# KranPowerV2_1.net
KiCad netlist of a schematic drawn in EAGLE
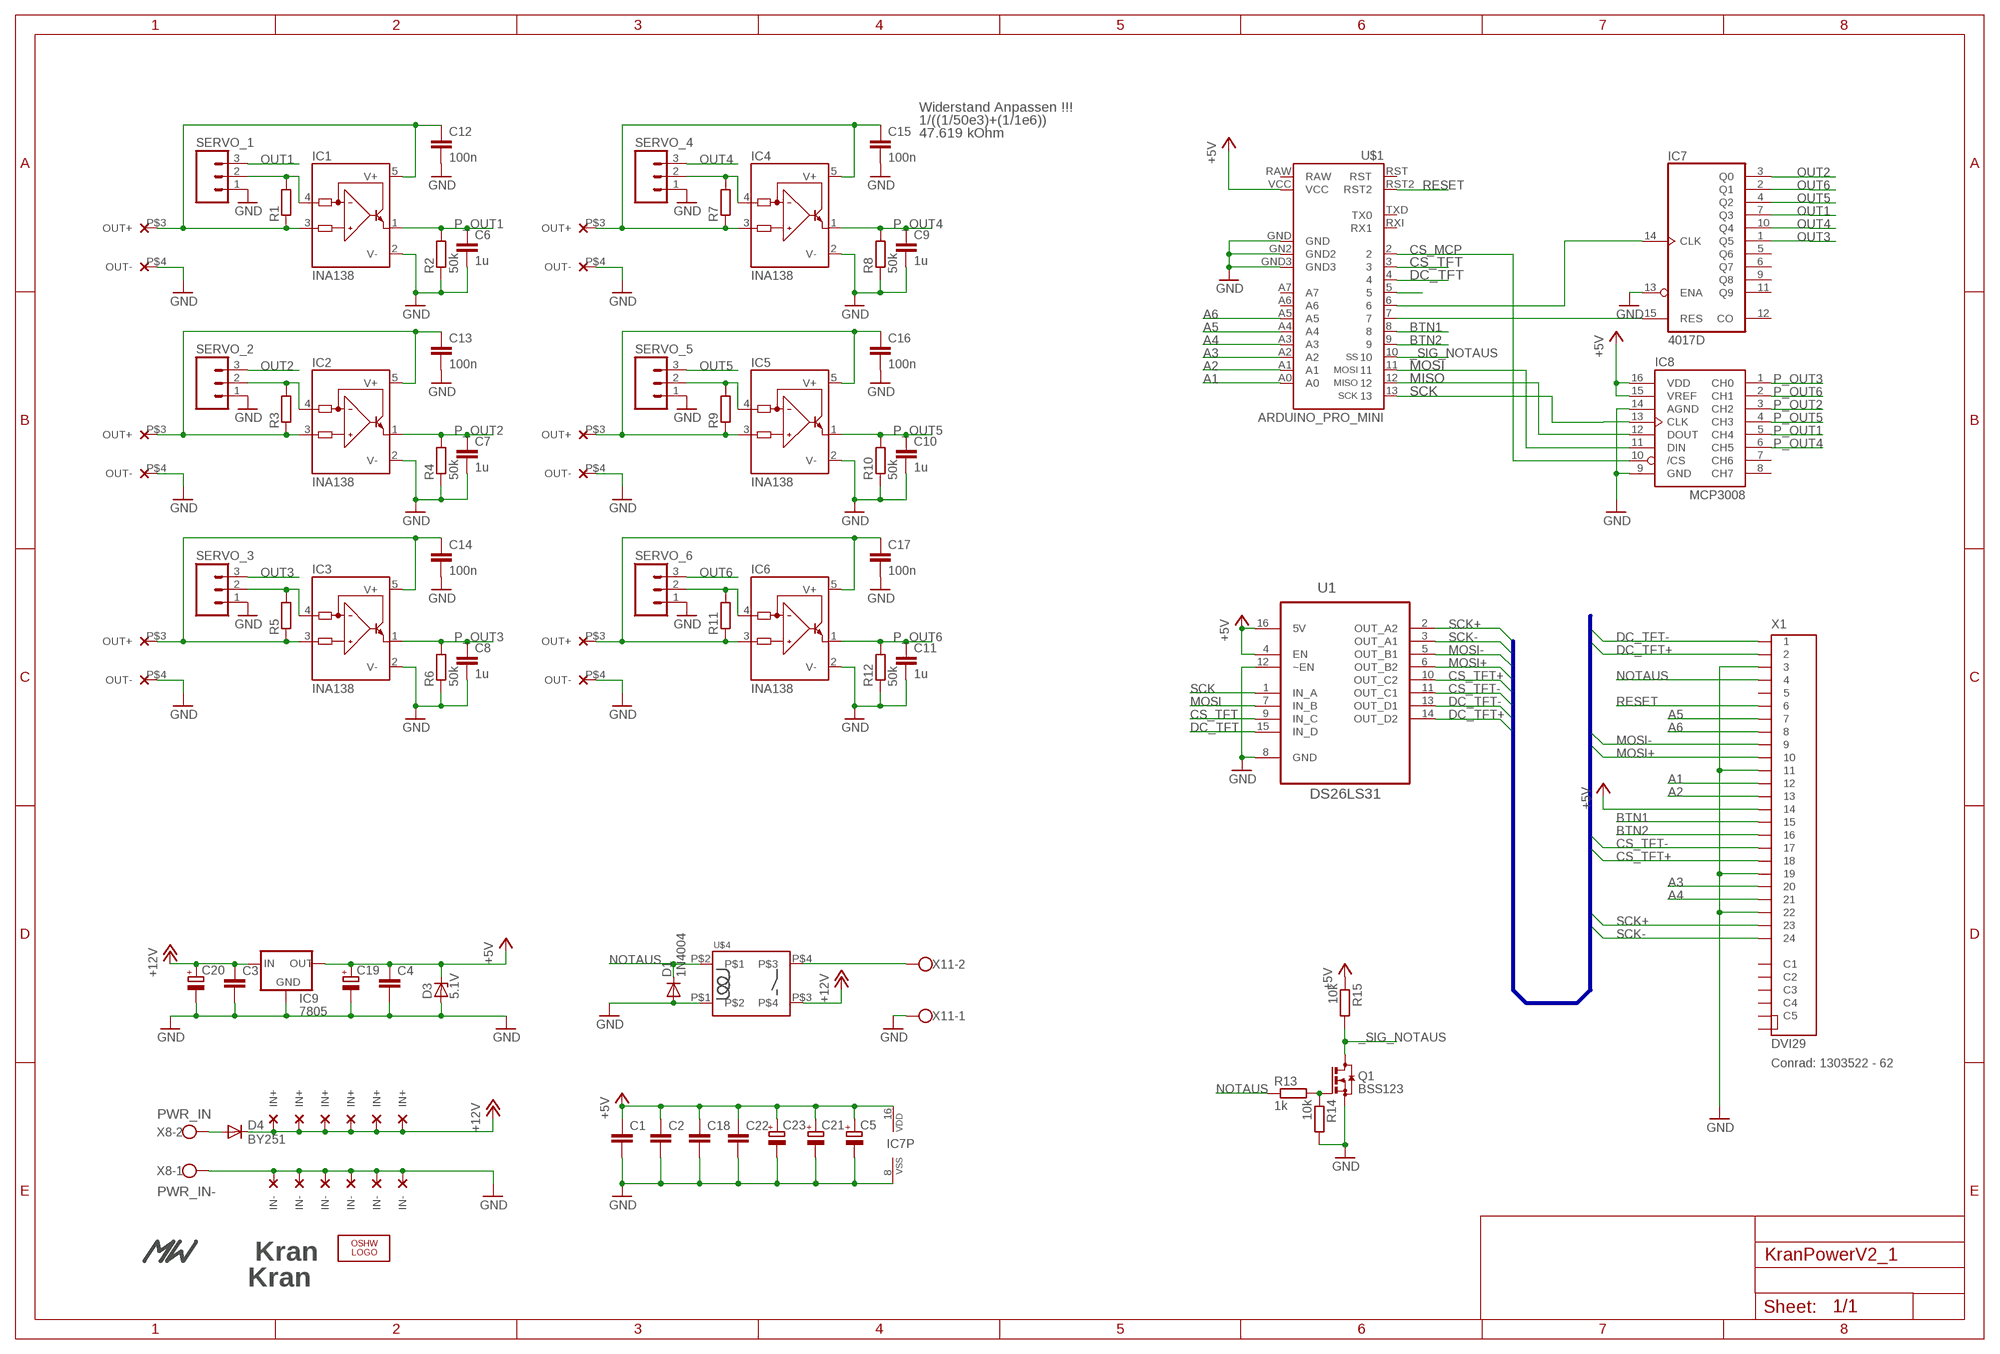
[diagram p0: schematic, sheet 1]

(export (version "E")
  (design (tool "Eeschema 10.0.6"))
  (components
    (comp (ref "C1")
      (value "C-EUC0603")
      (footprint "eagle-import:C0603")
      (libsource (lib "eagle-import") (part "C-EUC0603"))
    )
    (comp (ref "C2")
      (value "C-EUC0603")
      (footprint "eagle-import:C0603")
      (libsource (lib "eagle-import") (part "C-EUC0603"))
    )
    (comp (ref "C3")
      (value "C-EUC0603")
      (footprint "eagle-import:C0603")
      (libsource (lib "eagle-import") (part "C-EUC0603"))
    )
    (comp (ref "C4")
      (value "C-EUC0603")
      (footprint "eagle-import:C0603")
      (libsource (lib "eagle-import") (part "C-EUC0603"))
    )
    (comp (ref "C5")
      (value "CPOL-EUSMCB")
      (footprint "eagle-import:SMC_B")
      (libsource (lib "eagle-import") (part "CPOL-EUSMCB"))
    )
    (comp (ref "C6")
      (value "1u")
      (footprint "eagle-import:C0603")
      (libsource (lib "eagle-import") (part "C-EUC0603"))
    )
    (comp (ref "C7")
      (value "1u")
      (footprint "eagle-import:C0603")
      (libsource (lib "eagle-import") (part "C-EUC0603"))
    )
    (comp (ref "C8")
      (value "1u")
      (footprint "eagle-import:C0603")
      (libsource (lib "eagle-import") (part "C-EUC0603"))
    )
    (comp (ref "C9")
      (value "1u")
      (footprint "eagle-import:C0603")
      (libsource (lib "eagle-import") (part "C-EUC0603"))
    )
    (comp (ref "C10")
      (value "1u")
      (footprint "eagle-import:C0603")
      (libsource (lib "eagle-import") (part "C-EUC0603"))
    )
    (comp (ref "C11")
      (value "1u")
      (footprint "eagle-import:C0603")
      (libsource (lib "eagle-import") (part "C-EUC0603"))
    )
    (comp (ref "C12")
      (value "100n")
      (footprint "eagle-import:C0603")
      (libsource (lib "eagle-import") (part "C-EUC0603"))
    )
    (comp (ref "C13")
      (value "100n")
      (footprint "eagle-import:C0603")
      (libsource (lib "eagle-import") (part "C-EUC0603"))
    )
    (comp (ref "C14")
      (value "100n")
      (footprint "eagle-import:C0603")
      (libsource (lib "eagle-import") (part "C-EUC0603"))
    )
    (comp (ref "C15")
      (value "100n")
      (footprint "eagle-import:C0603")
      (libsource (lib "eagle-import") (part "C-EUC0603"))
    )
    (comp (ref "C16")
      (value "100n")
      (footprint "eagle-import:C0603")
      (libsource (lib "eagle-import") (part "C-EUC0603"))
    )
    (comp (ref "C17")
      (value "100n")
      (footprint "eagle-import:C0603")
      (libsource (lib "eagle-import") (part "C-EUC0603"))
    )
    (comp (ref "C18")
      (value "C-EUC0603")
      (footprint "eagle-import:C0603")
      (libsource (lib "eagle-import") (part "C-EUC0603"))
    )
    (comp (ref "C19")
      (value "CPOL-EUSMCB")
      (footprint "eagle-import:SMC_B")
      (libsource (lib "eagle-import") (part "CPOL-EUSMCB"))
    )
    (comp (ref "C20")
      (value "CPOL-EUSMCB")
      (footprint "eagle-import:SMC_B")
      (libsource (lib "eagle-import") (part "CPOL-EUSMCB"))
    )
    (comp (ref "C21")
      (value "CPOL-EUSMCB")
      (footprint "eagle-import:SMC_B")
      (libsource (lib "eagle-import") (part "CPOL-EUSMCB"))
    )
    (comp (ref "C22")
      (value "C-EUC0603")
      (footprint "eagle-import:C0603")
      (libsource (lib "eagle-import") (part "C-EUC0603"))
    )
    (comp (ref "C23")
      (value "CPOL-EUSMCB")
      (footprint "eagle-import:SMC_B")
      (libsource (lib "eagle-import") (part "CPOL-EUSMCB"))
    )
    (comp (ref "D1")
      (value "1N4004")
      (footprint "eagle-import:DO41-10")
      (libsource (lib "eagle-import") (part "1N4004"))
    )
    (comp (ref "D3")
      (value "5.1V")
      (footprint "eagle-import:DO34Z7")
      (libsource (lib "eagle-import") (part "ZENER-DIODEDO34-7"))
    )
    (comp (ref "D4")
      (value "BY251")
      (footprint "eagle-import:DO201-15")
      (libsource (lib "eagle-import") (part "BY251"))
    )
    (comp (ref "IC1")
      (value "INA138")
      (footprint "eagle-import:SOT23-5")
      (fields (field (name "MF") "TEXAS INSTRUMENTS") (field (name "MPN") "INA138NA/250"))
      (libsource (lib "eagle-import") (part "INA138"))
    )
    (comp (ref "IC2")
      (value "INA138")
      (footprint "eagle-import:SOT23-5")
      (fields (field (name "MF") "TEXAS INSTRUMENTS") (field (name "MPN") "INA138NA/250"))
      (libsource (lib "eagle-import") (part "INA138"))
    )
    (comp (ref "IC3")
      (value "INA138")
      (footprint "eagle-import:SOT23-5")
      (fields (field (name "MF") "TEXAS INSTRUMENTS") (field (name "MPN") "INA138NA/250"))
      (libsource (lib "eagle-import") (part "INA138"))
    )
    (comp (ref "IC4")
      (value "INA138")
      (footprint "eagle-import:SOT23-5")
      (fields (field (name "MF") "TEXAS INSTRUMENTS") (field (name "MPN") "INA138NA/250"))
      (libsource (lib "eagle-import") (part "INA138"))
    )
    (comp (ref "IC5")
      (value "INA138")
      (footprint "eagle-import:SOT23-5")
      (fields (field (name "MF") "TEXAS INSTRUMENTS") (field (name "MPN") "INA138NA/250"))
      (libsource (lib "eagle-import") (part "INA138"))
    )
    (comp (ref "IC6")
      (value "INA138")
      (footprint "eagle-import:SOT23-5")
      (fields (field (name "MF") "TEXAS INSTRUMENTS") (field (name "MPN") "INA138NA/250"))
      (libsource (lib "eagle-import") (part "INA138"))
    )
    (comp (ref "IC7")
      (value "4017D")
      (footprint "eagle-import:SO16")
      (libsource (lib "eagle-import") (part "4017D"))
    )
    (comp (ref "IC8")
      (value "MCP3008")
      (footprint "eagle-import:SO16")
      (libsource (lib "eagle-import") (part "MCP3008"))
    )
    (comp (ref "IC9")
      (value "7805")
      (footprint "eagle-import:78XXL")
      (libsource (lib "eagle-import") (part "V_REG_78XXSIDE"))
    )
    (comp (ref "LOGO1")
      (value "OSHW_LOGO_FILLX0350-NT")
      (footprint "eagle-import:OSHW_FILLX350_NOTEXT")
      (libsource (lib "eagle-import") (part "OSHW_LOGO_FILLX0350-NT"))
    )
    (comp (ref "Q1")
      (value "BSS123")
      (footprint "eagle-import:SOT23")
      (libsource (lib "eagle-import") (part "BSS123"))
    )
    (comp (ref "R1")
      (value "R-EU_R2512")
      (footprint "eagle-import:R2512")
      (libsource (lib "eagle-import") (part "R-EU_R2512"))
    )
    (comp (ref "R2")
      (value "50k")
      (footprint "eagle-import:R0603")
      (libsource (lib "eagle-import") (part "R-EU_R0603"))
    )
    (comp (ref "R3")
      (value "R-EU_R2512")
      (footprint "eagle-import:R2512")
      (libsource (lib "eagle-import") (part "R-EU_R2512"))
    )
    (comp (ref "R4")
      (value "50k")
      (footprint "eagle-import:R0603")
      (libsource (lib "eagle-import") (part "R-EU_R0603"))
    )
    (comp (ref "R5")
      (value "R-EU_R2512")
      (footprint "eagle-import:R2512")
      (libsource (lib "eagle-import") (part "R-EU_R2512"))
    )
    (comp (ref "R6")
      (value "50k")
      (footprint "eagle-import:R0603")
      (libsource (lib "eagle-import") (part "R-EU_R0603"))
    )
    (comp (ref "R7")
      (value "R-EU_R2512")
      (footprint "eagle-import:R2512")
      (libsource (lib "eagle-import") (part "R-EU_R2512"))
    )
    (comp (ref "R8")
      (value "50k")
      (footprint "eagle-import:R0603")
      (libsource (lib "eagle-import") (part "R-EU_R0603"))
    )
    (comp (ref "R9")
      (value "R-EU_R2512")
      (footprint "eagle-import:R2512")
      (libsource (lib "eagle-import") (part "R-EU_R2512"))
    )
    (comp (ref "R10")
      (value "50k")
      (footprint "eagle-import:R0603")
      (libsource (lib "eagle-import") (part "R-EU_R0603"))
    )
    (comp (ref "R11")
      (value "R-EU_R2512")
      (footprint "eagle-import:R2512")
      (libsource (lib "eagle-import") (part "R-EU_R2512"))
    )
    (comp (ref "R12")
      (value "50k")
      (footprint "eagle-import:R0603")
      (libsource (lib "eagle-import") (part "R-EU_R0603"))
    )
    (comp (ref "R13")
      (value "1k")
      (footprint "eagle-import:R0603")
      (libsource (lib "eagle-import") (part "R-EU_R0603"))
    )
    (comp (ref "R14")
      (value "10k")
      (footprint "eagle-import:R0603")
      (libsource (lib "eagle-import") (part "R-EU_R0603"))
    )
    (comp (ref "R15")
      (value "10k")
      (footprint "eagle-import:R0603")
      (libsource (lib "eagle-import") (part "R-EU_R0603"))
    )
    (comp (ref "SERVO_1")
      (value "M03LOCK")
      (footprint "eagle-import:1X03_LOCK")
      (libsource (lib "eagle-import") (part "M03LOCK"))
    )
    (comp (ref "SERVO_2")
      (value "M03LOCK")
      (footprint "eagle-import:1X03_LOCK")
      (libsource (lib "eagle-import") (part "M03LOCK"))
    )
    (comp (ref "SERVO_3")
      (value "M03LOCK")
      (footprint "eagle-import:1X03_LOCK")
      (libsource (lib "eagle-import") (part "M03LOCK"))
    )
    (comp (ref "SERVO_4")
      (value "M03LOCK")
      (footprint "eagle-import:1X03_LOCK")
      (libsource (lib "eagle-import") (part "M03LOCK"))
    )
    (comp (ref "SERVO_5")
      (value "M03LOCK")
      (footprint "eagle-import:1X03_LOCK")
      (libsource (lib "eagle-import") (part "M03LOCK"))
    )
    (comp (ref "SERVO_6")
      (value "M03LOCK")
      (footprint "eagle-import:1X03_LOCK")
      (libsource (lib "eagle-import") (part "M03LOCK"))
    )
    (comp (ref "U$1")
      (value "ARDUINO_PRO_MINI")
      (footprint "eagle-import:ARDUINO_PRO_MINI")
      (libsource (lib "eagle-import") (part "ARDUINO_PRO_MINI"))
    )
    (comp (ref "U$2")
      (value "MW_LOGO")
      (footprint "eagle-import:MW_11X5MM")
      (libsource (lib "eagle-import") (part "MW_LOGO"))
    )
    (comp (ref "U$3")
      (value "KRAN_LOGO")
      (footprint "eagle-import:KRAN_LOGO")
      (libsource (lib "eagle-import") (part "KRAN_LOGO"))
    )
    (comp (ref "U$4")
      (value "RELAY_ZETTLER_AZ767")
      (footprint "eagle-import:RELAY_ZETTLER_AZ767")
      (libsource (lib "eagle-import") (part "RELAY_ZETTLER_AZ767"))
    )
    (comp (ref "U$5")
      (value "LM2596_STEPDOWN")
      (footprint "eagle-import:LM2596_STEPDOWN")
      (libsource (lib "eagle-import") (part "LM2596_STEPDOWN"))
    )
    (comp (ref "U$6")
      (value "LM2596_STEPDOWN")
      (footprint "eagle-import:LM2596_STEPDOWN")
      (libsource (lib "eagle-import") (part "LM2596_STEPDOWN"))
    )
    (comp (ref "U$7")
      (value "LM2596_STEPDOWN")
      (footprint "eagle-import:LM2596_STEPDOWN")
      (libsource (lib "eagle-import") (part "LM2596_STEPDOWN"))
    )
    (comp (ref "U$8")
      (value "LM2596_STEPDOWN")
      (footprint "eagle-import:LM2596_STEPDOWN")
      (libsource (lib "eagle-import") (part "LM2596_STEPDOWN"))
    )
    (comp (ref "U$9")
      (value "LM2596_STEPDOWN")
      (footprint "eagle-import:LM2596_STEPDOWN")
      (libsource (lib "eagle-import") (part "LM2596_STEPDOWN"))
    )
    (comp (ref "U$10")
      (value "LM2596_STEPDOWN")
      (footprint "eagle-import:LM2596_STEPDOWN")
      (libsource (lib "eagle-import") (part "LM2596_STEPDOWN"))
    )
    (comp (ref "U$13")
      (value "KRAN_LOGO")
      (footprint "eagle-import:KRAN_LOGO")
      (libsource (lib "eagle-import") (part "KRAN_LOGO"))
    )
    (comp (ref "U1")
      (value "DS26LS31")
      (footprint "eagle-import:SOIC127P600X175-16N")
      (fields (field (name "MPN") "DS26LS31CM"))
      (libsource (lib "eagle-import") (part "DS26LS31CM"))
    )
    (comp (ref "X1")
      (value "DVI29")
      (footprint "eagle-import:CCDVI-29DVISIR-A-2")
      (libsource (lib "eagle-import") (part "DVI29"))
    )
    (comp (ref "X8")
      (value "W237-102")
      (footprint "eagle-import:W237-102")
      (fields (field (name "MPN") "237-102"))
      (libsource (lib "eagle-import") (part "W237-102"))
    )
    (comp (ref "X11")
      (value "W237-102")
      (footprint "eagle-import:W237-102")
      (fields (field (name "MPN") "237-102"))
      (libsource (lib "eagle-import") (part "W237-102"))
    )
  )
  (nets
    (net (code "1") (name "+5V") (class "Default")
      (node (ref "C1") (pin "1") (pinfunction "1_1") (pintype "passive"))
      (node (ref "C18") (pin "1") (pinfunction "1_1") (pintype "passive"))
      (node (ref "C19") (pin "+") (pinfunction "+_+") (pintype "passive"))
      (node (ref "C2") (pin "1") (pinfunction "1_1") (pintype "passive"))
      (node (ref "C21") (pin "+") (pinfunction "+_+") (pintype "passive"))
      (node (ref "C22") (pin "1") (pinfunction "1_1") (pintype "passive"))
      (node (ref "C23") (pin "+") (pinfunction "+_+") (pintype "passive"))
      (node (ref "C4") (pin "1") (pinfunction "1_1") (pintype "passive"))
      (node (ref "C5") (pin "+") (pinfunction "+_+") (pintype "passive"))
      (node (ref "D3") (pin "C") (pinfunction "C_C") (pintype "passive"))
      (node (ref "IC7") (pin "16") (pinfunction "VDD_16") (pintype "power_in"))
      (node (ref "IC8") (pin "15") (pinfunction "VREF_15") (pintype "input"))
      (node (ref "IC8") (pin "16") (pinfunction "VDD_16") (pintype "power_in"))
      (node (ref "IC9") (pin "OUT") (pinfunction "OUT_OUT") (pintype "output"))
      (node (ref "R15") (pin "1") (pinfunction "1_1") (pintype "passive"))
      (node (ref "U$1") (pin "VCC") (pinfunction "VCC_VCC") (pintype "bidirectional"))
      (node (ref "U1") (pin "16") (pinfunction "5V_16") (pintype "power_in"))
      (node (ref "U1") (pin "4") (pinfunction "EN_4") (pintype "input"))
      (node (ref "X1") (pin "14") (pinfunction "14_14") (pintype "passive"))
    )
    (net (code "2") (name "+12V") (class "Default")
      (node (ref "C20") (pin "+") (pinfunction "+_+") (pintype "passive"))
      (node (ref "C3") (pin "1") (pinfunction "1_1") (pintype "passive"))
      (node (ref "D4") (pin "C") (pinfunction "C_C") (pintype "passive"))
      (node (ref "IC9") (pin "IN") (pinfunction "IN_IN") (pintype "input"))
      (node (ref "U$10") (pin "P$1") (pinfunction "IN+_P$1") (pintype "bidirectional"))
      (node (ref "U$4") (pin "P$3") (pinfunction "P$4_P$3") (pintype "bidirectional"))
      (node (ref "U$5") (pin "P$1") (pinfunction "IN+_P$1") (pintype "bidirectional"))
      (node (ref "U$6") (pin "P$1") (pinfunction "IN+_P$1") (pintype "bidirectional"))
      (node (ref "U$7") (pin "P$1") (pinfunction "IN+_P$1") (pintype "bidirectional"))
      (node (ref "U$8") (pin "P$1") (pinfunction "IN+_P$1") (pintype "bidirectional"))
      (node (ref "U$9") (pin "P$1") (pinfunction "IN+_P$1") (pintype "bidirectional"))
    )
    (net (code "3") (name "/A1") (class "Default")
      (node (ref "U$1") (pin "A0") (pinfunction "A0_A0") (pintype "bidirectional"))
      (node (ref "X1") (pin "12") (pinfunction "12_12") (pintype "passive"))
    )
    (net (code "4") (name "/A2") (class "Default")
      (node (ref "U$1") (pin "A1") (pinfunction "A1_A1") (pintype "bidirectional"))
      (node (ref "X1") (pin "13") (pinfunction "13_13") (pintype "passive"))
    )
    (net (code "5") (name "/A3") (class "Default")
      (node (ref "U$1") (pin "A2") (pinfunction "A2_A2") (pintype "bidirectional"))
      (node (ref "X1") (pin "20") (pinfunction "20_20") (pintype "passive"))
    )
    (net (code "6") (name "/A4") (class "Default")
      (node (ref "U$1") (pin "A3") (pinfunction "A3_A3") (pintype "bidirectional"))
      (node (ref "X1") (pin "21") (pinfunction "21_21") (pintype "passive"))
    )
    (net (code "7") (name "/A5") (class "Default")
      (node (ref "U$1") (pin "A4") (pinfunction "A4_A4") (pintype "bidirectional"))
      (node (ref "X1") (pin "7") (pinfunction "7_7") (pintype "passive"))
    )
    (net (code "8") (name "/A6") (class "Default")
      (node (ref "U$1") (pin "A5") (pinfunction "A5_A5") (pintype "bidirectional"))
      (node (ref "X1") (pin "8") (pinfunction "8_8") (pintype "passive"))
    )
    (net (code "9") (name "/BTN1") (class "Default")
      (node (ref "U$1") (pin "8") (pinfunction "8_8") (pintype "bidirectional"))
      (node (ref "X1") (pin "15") (pinfunction "15_15") (pintype "passive"))
    )
    (net (code "10") (name "/BTN2") (class "Default")
      (node (ref "U$1") (pin "9") (pinfunction "9_9") (pintype "bidirectional"))
      (node (ref "X1") (pin "16") (pinfunction "16_16") (pintype "passive"))
    )
    (net (code "11") (name "/CS_MCP") (class "Default")
      (node (ref "IC8") (pin "10") (pinfunction "/CS_10") (pintype "input"))
      (node (ref "U$1") (pin "2") (pinfunction "2_2") (pintype "bidirectional"))
    )
    (net (code "12") (name "/CS_TFT") (class "Default")
      (node (ref "U$1") (pin "3") (pinfunction "3_3") (pintype "bidirectional"))
      (node (ref "U1") (pin "9") (pinfunction "IN_C_9") (pintype "input"))
    )
    (net (code "13") (name "/CS_TFT+") (class "Default")
      (node (ref "U1") (pin "10") (pinfunction "OUT_C2_10") (pintype "output"))
      (node (ref "X1") (pin "18") (pinfunction "18_18") (pintype "passive"))
    )
    (net (code "14") (name "/CS_TFT-") (class "Default")
      (node (ref "U1") (pin "11") (pinfunction "OUT_C1_11") (pintype "output"))
      (node (ref "X1") (pin "17") (pinfunction "17_17") (pintype "passive"))
    )
    (net (code "15") (name "/DC_TFT") (class "Default")
      (node (ref "U$1") (pin "4") (pinfunction "4_4") (pintype "bidirectional"))
      (node (ref "U1") (pin "15") (pinfunction "IN_D_15") (pintype "input"))
    )
    (net (code "16") (name "/DC_TFT+") (class "Default")
      (node (ref "U1") (pin "14") (pinfunction "OUT_D2_14") (pintype "output"))
      (node (ref "X1") (pin "2") (pinfunction "2_2") (pintype "passive"))
    )
    (net (code "17") (name "/DC_TFT-") (class "Default")
      (node (ref "U1") (pin "13") (pinfunction "OUT_D1_13") (pintype "output"))
      (node (ref "X1") (pin "1") (pinfunction "1_1") (pintype "passive"))
    )
    (net (code "18") (name "/MISO") (class "Default")
      (node (ref "IC8") (pin "12") (pinfunction "DOUT_12") (pintype "output"))
      (node (ref "U$1") (pin "12") (pinfunction "12_12") (pintype "bidirectional"))
    )
    (net (code "19") (name "/MOSI") (class "Default")
      (node (ref "IC8") (pin "11") (pinfunction "DIN_11") (pintype "input"))
      (node (ref "U$1") (pin "11") (pinfunction "11_11") (pintype "bidirectional"))
      (node (ref "U1") (pin "7") (pinfunction "IN_B_7") (pintype "input"))
    )
    (net (code "20") (name "/MOSI+") (class "Default")
      (node (ref "U1") (pin "6") (pinfunction "OUT_B2_6") (pintype "output"))
      (node (ref "X1") (pin "10") (pinfunction "10_10") (pintype "passive"))
    )
    (net (code "21") (name "/MOSI-") (class "Default")
      (node (ref "U1") (pin "5") (pinfunction "OUT_B1_5") (pintype "output"))
      (node (ref "X1") (pin "9") (pinfunction "9_9") (pintype "passive"))
    )
    (net (code "22") (name "/NOTAUS") (class "Default")
      (node (ref "D1") (pin "C") (pinfunction "C_C") (pintype "passive"))
      (node (ref "R13") (pin "1") (pinfunction "1_1") (pintype "passive"))
      (node (ref "U$4") (pin "P$2") (pinfunction "P$1_P$2") (pintype "bidirectional"))
      (node (ref "X1") (pin "4") (pinfunction "4_4") (pintype "passive"))
    )
    (net (code "23") (name "/OUT1") (class "Default")
      (node (ref "IC7") (pin "7") (pinfunction "Q3_7") (pintype "output"))
      (node (ref "SERVO_1") (pin "3") (pinfunction "3_3") (pintype "passive"))
    )
    (net (code "24") (name "/OUT2") (class "Default")
      (node (ref "IC7") (pin "3") (pinfunction "Q0_3") (pintype "output"))
      (node (ref "SERVO_2") (pin "3") (pinfunction "3_3") (pintype "passive"))
    )
    (net (code "25") (name "/OUT3") (class "Default")
      (node (ref "IC7") (pin "1") (pinfunction "Q5_1") (pintype "output"))
      (node (ref "SERVO_3") (pin "3") (pinfunction "3_3") (pintype "passive"))
    )
    (net (code "26") (name "/OUT4") (class "Default")
      (node (ref "IC7") (pin "10") (pinfunction "Q4_10") (pintype "output"))
      (node (ref "SERVO_4") (pin "3") (pinfunction "3_3") (pintype "passive"))
    )
    (net (code "27") (name "/OUT5") (class "Default")
      (node (ref "IC7") (pin "4") (pinfunction "Q2_4") (pintype "output"))
      (node (ref "SERVO_5") (pin "3") (pinfunction "3_3") (pintype "passive"))
    )
    (net (code "28") (name "/OUT6") (class "Default")
      (node (ref "IC7") (pin "2") (pinfunction "Q1_2") (pintype "output"))
      (node (ref "SERVO_6") (pin "3") (pinfunction "3_3") (pintype "passive"))
    )
    (net (code "29") (name "/P_OUT1") (class "Default")
      (node (ref "C6") (pin "1") (pinfunction "1_1") (pintype "passive"))
      (node (ref "IC1") (pin "1") (pinfunction "OUT_1") (pintype "output"))
      (node (ref "IC8") (pin "5") (pinfunction "CH4_5") (pintype "input"))
      (node (ref "R2") (pin "2") (pinfunction "2_2") (pintype "passive"))
    )
    (net (code "30") (name "/P_OUT2") (class "Default")
      (node (ref "C7") (pin "1") (pinfunction "1_1") (pintype "passive"))
      (node (ref "IC2") (pin "1") (pinfunction "OUT_1") (pintype "output"))
      (node (ref "IC8") (pin "3") (pinfunction "CH2_3") (pintype "input"))
      (node (ref "R4") (pin "2") (pinfunction "2_2") (pintype "passive"))
    )
    (net (code "31") (name "/P_OUT3") (class "Default")
      (node (ref "C8") (pin "1") (pinfunction "1_1") (pintype "passive"))
      (node (ref "IC3") (pin "1") (pinfunction "OUT_1") (pintype "output"))
      (node (ref "IC8") (pin "1") (pinfunction "CH0_1") (pintype "input"))
      (node (ref "R6") (pin "2") (pinfunction "2_2") (pintype "passive"))
    )
    (net (code "32") (name "/P_OUT4") (class "Default")
      (node (ref "C9") (pin "1") (pinfunction "1_1") (pintype "passive"))
      (node (ref "IC4") (pin "1") (pinfunction "OUT_1") (pintype "output"))
      (node (ref "IC8") (pin "6") (pinfunction "CH5_6") (pintype "input"))
      (node (ref "R8") (pin "2") (pinfunction "2_2") (pintype "passive"))
    )
    (net (code "33") (name "/P_OUT5") (class "Default")
      (node (ref "C10") (pin "1") (pinfunction "1_1") (pintype "passive"))
      (node (ref "IC5") (pin "1") (pinfunction "OUT_1") (pintype "output"))
      (node (ref "IC8") (pin "4") (pinfunction "CH3_4") (pintype "input"))
      (node (ref "R10") (pin "2") (pinfunction "2_2") (pintype "passive"))
    )
    (net (code "34") (name "/P_OUT6") (class "Default")
      (node (ref "C11") (pin "1") (pinfunction "1_1") (pintype "passive"))
      (node (ref "IC6") (pin "1") (pinfunction "OUT_1") (pintype "output"))
      (node (ref "IC8") (pin "2") (pinfunction "CH1_2") (pintype "input"))
      (node (ref "R12") (pin "2") (pinfunction "2_2") (pintype "passive"))
    )
    (net (code "35") (name "/RESET") (class "Default")
      (node (ref "U$1") (pin "RST2") (pinfunction "RST2_RST2") (pintype "bidirectional"))
      (node (ref "X1") (pin "6") (pinfunction "6_6") (pintype "passive"))
    )
    (net (code "36") (name "/SCK") (class "Default")
      (node (ref "IC8") (pin "13") (pinfunction "CLK_13") (pintype "input"))
      (node (ref "U$1") (pin "13") (pinfunction "13_13") (pintype "bidirectional"))
      (node (ref "U1") (pin "1") (pinfunction "IN_A_1") (pintype "input"))
    )
    (net (code "37") (name "/SCK+") (class "Default")
      (node (ref "U1") (pin "2") (pinfunction "OUT_A2_2") (pintype "output"))
      (node (ref "X1") (pin "23") (pinfunction "23_23") (pintype "passive"))
    )
    (net (code "38") (name "/SCK-") (class "Default")
      (node (ref "U1") (pin "3") (pinfunction "OUT_A1_3") (pintype "output"))
      (node (ref "X1") (pin "24") (pinfunction "24_24") (pintype "passive"))
    )
    (net (code "39") (name "/_SIG_NOTAUS") (class "Default")
      (node (ref "Q1") (pin "3") (pinfunction "D_3") (pintype "passive"))
      (node (ref "R15") (pin "2") (pinfunction "2_2") (pintype "passive"))
      (node (ref "U$1") (pin "10") (pinfunction "10_10") (pintype "bidirectional"))
    )
    (net (code "40") (name "GND") (class "Default")
      (node (ref "C1") (pin "2") (pinfunction "2_2") (pintype "passive"))
      (node (ref "C10") (pin "2") (pinfunction "2_2") (pintype "passive"))
      (node (ref "C11") (pin "2") (pinfunction "2_2") (pintype "passive"))
      (node (ref "C12") (pin "2") (pinfunction "2_2") (pintype "passive"))
      (node (ref "C13") (pin "2") (pinfunction "2_2") (pintype "passive"))
      (node (ref "C14") (pin "2") (pinfunction "2_2") (pintype "passive"))
      (node (ref "C15") (pin "2") (pinfunction "2_2") (pintype "passive"))
      (node (ref "C16") (pin "2") (pinfunction "2_2") (pintype "passive"))
      (node (ref "C17") (pin "2") (pinfunction "2_2") (pintype "passive"))
      (node (ref "C18") (pin "2") (pinfunction "2_2") (pintype "passive"))
      (node (ref "C19") (pin "-") (pinfunction "-_-") (pintype "passive"))
      (node (ref "C2") (pin "2") (pinfunction "2_2") (pintype "passive"))
      (node (ref "C20") (pin "-") (pinfunction "-_-") (pintype "passive"))
      (node (ref "C21") (pin "-") (pinfunction "-_-") (pintype "passive"))
      (node (ref "C22") (pin "2") (pinfunction "2_2") (pintype "passive"))
      (node (ref "C23") (pin "-") (pinfunction "-_-") (pintype "passive"))
      (node (ref "C3") (pin "2") (pinfunction "2_2") (pintype "passive"))
      (node (ref "C4") (pin "2") (pinfunction "2_2") (pintype "passive"))
      (node (ref "C5") (pin "-") (pinfunction "-_-") (pintype "passive"))
      (node (ref "C6") (pin "2") (pinfunction "2_2") (pintype "passive"))
      (node (ref "C7") (pin "2") (pinfunction "2_2") (pintype "passive"))
      (node (ref "C8") (pin "2") (pinfunction "2_2") (pintype "passive"))
      (node (ref "C9") (pin "2") (pinfunction "2_2") (pintype "passive"))
      (node (ref "D1") (pin "A") (pinfunction "A_A") (pintype "passive"))
      (node (ref "D3") (pin "A") (pinfunction "A_A") (pintype "passive"))
      (node (ref "IC1") (pin "2") (pinfunction "V-_2") (pintype "power_in"))
      (node (ref "IC2") (pin "2") (pinfunction "V-_2") (pintype "power_in"))
      (node (ref "IC3") (pin "2") (pinfunction "V-_2") (pintype "power_in"))
      (node (ref "IC4") (pin "2") (pinfunction "V-_2") (pintype "power_in"))
      (node (ref "IC5") (pin "2") (pinfunction "V-_2") (pintype "power_in"))
      (node (ref "IC6") (pin "2") (pinfunction "V-_2") (pintype "power_in"))
      (node (ref "IC7") (pin "13") (pinfunction "ENA_13") (pintype "input"))
      (node (ref "IC7") (pin "8") (pinfunction "VSS_8") (pintype "power_in"))
      (node (ref "IC8") (pin "14") (pinfunction "AGND_14") (pintype "power_in"))
      (node (ref "IC8") (pin "9") (pinfunction "GND_9") (pintype "power_in"))
      (node (ref "IC9") (pin "GND") (pinfunction "GND_GND") (pintype "input"))
      (node (ref "Q1") (pin "2") (pinfunction "S_2") (pintype "passive"))
      (node (ref "R10") (pin "1") (pinfunction "1_1") (pintype "passive"))
      (node (ref "R12") (pin "1") (pinfunction "1_1") (pintype "passive"))
      (node (ref "R14") (pin "2") (pinfunction "2_2") (pintype "passive"))
      (node (ref "R2") (pin "1") (pinfunction "1_1") (pintype "passive"))
      (node (ref "R4") (pin "1") (pinfunction "1_1") (pintype "passive"))
      (node (ref "R6") (pin "1") (pinfunction "1_1") (pintype "passive"))
      (node (ref "R8") (pin "1") (pinfunction "1_1") (pintype "passive"))
      (node (ref "SERVO_1") (pin "1") (pinfunction "1_1") (pintype "passive"))
      (node (ref "SERVO_2") (pin "1") (pinfunction "1_1") (pintype "passive"))
      (node (ref "SERVO_3") (pin "1") (pinfunction "1_1") (pintype "passive"))
      (node (ref "SERVO_4") (pin "1") (pinfunction "1_1") (pintype "passive"))
      (node (ref "SERVO_5") (pin "1") (pinfunction "1_1") (pintype "passive"))
      (node (ref "SERVO_6") (pin "1") (pinfunction "1_1") (pintype "passive"))
      (node (ref "U$1") (pin "GN2") (pinfunction "GND2_GN2") (pintype "bidirectional"))
      (node (ref "U$1") (pin "GND") (pinfunction "GND_GND") (pintype "bidirectional"))
      (node (ref "U$1") (pin "GND3") (pinfunction "GND3_GND3") (pintype "bidirectional"))
      (node (ref "U$10") (pin "P$2") (pinfunction "IN-_P$2") (pintype "bidirectional"))
      (node (ref "U$10") (pin "P$4") (pinfunction "OUT-_P$4") (pintype "bidirectional"))
      (node (ref "U$4") (pin "P$1") (pinfunction "P$2_P$1") (pintype "bidirectional"))
      (node (ref "U$5") (pin "P$2") (pinfunction "IN-_P$2") (pintype "bidirectional"))
      (node (ref "U$5") (pin "P$4") (pinfunction "OUT-_P$4") (pintype "bidirectional"))
      (node (ref "U$6") (pin "P$2") (pinfunction "IN-_P$2") (pintype "bidirectional"))
      (node (ref "U$6") (pin "P$4") (pinfunction "OUT-_P$4") (pintype "bidirectional"))
      (node (ref "U$7") (pin "P$2") (pinfunction "IN-_P$2") (pintype "bidirectional"))
      (node (ref "U$7") (pin "P$4") (pinfunction "OUT-_P$4") (pintype "bidirectional"))
      (node (ref "U$8") (pin "P$2") (pinfunction "IN-_P$2") (pintype "bidirectional"))
      (node (ref "U$8") (pin "P$4") (pinfunction "OUT-_P$4") (pintype "bidirectional"))
      (node (ref "U$9") (pin "P$2") (pinfunction "IN-_P$2") (pintype "bidirectional"))
      (node (ref "U$9") (pin "P$4") (pinfunction "OUT-_P$4") (pintype "bidirectional"))
      (node (ref "U1") (pin "12") (pinfunction "~{EN}_12") (pintype "input"))
      (node (ref "U1") (pin "8") (pinfunction "GND_8") (pintype "passive"))
      (node (ref "X1") (pin "11") (pinfunction "11_11") (pintype "passive"))
      (node (ref "X1") (pin "19") (pinfunction "19_19") (pintype "passive"))
      (node (ref "X1") (pin "22") (pinfunction "22_22") (pintype "passive"))
      (node (ref "X1") (pin "3") (pinfunction "3_3") (pintype "passive"))
      (node (ref "X11") (pin "1") (pinfunction "KL_1") (pintype "passive"))
      (node (ref "X8") (pin "1") (pinfunction "KL_1") (pintype "passive"))
    )
    (net (code "41") (name "Net-(IC1-IN+)") (class "Default")
      (node (ref "C12") (pin "1") (pinfunction "1_1") (pintype "passive"))
      (node (ref "IC1") (pin "3") (pinfunction "IN+_3") (pintype "input"))
      (node (ref "IC1") (pin "5") (pinfunction "V+_5") (pintype "power_in"))
      (node (ref "R1") (pin "1") (pinfunction "1_1") (pintype "passive"))
      (node (ref "U$5") (pin "P$3") (pinfunction "OUT+_P$3") (pintype "bidirectional"))
    )
    (net (code "42") (name "Net-(IC1-IN-)") (class "Default")
      (node (ref "IC1") (pin "4") (pinfunction "IN-_4") (pintype "input"))
      (node (ref "R1") (pin "2") (pinfunction "2_2") (pintype "passive"))
      (node (ref "SERVO_1") (pin "2") (pinfunction "2_2") (pintype "passive"))
    )
    (net (code "43") (name "Net-(IC2-IN+)") (class "Default")
      (node (ref "C13") (pin "1") (pinfunction "1_1") (pintype "passive"))
      (node (ref "IC2") (pin "3") (pinfunction "IN+_3") (pintype "input"))
      (node (ref "IC2") (pin "5") (pinfunction "V+_5") (pintype "power_in"))
      (node (ref "R3") (pin "1") (pinfunction "1_1") (pintype "passive"))
      (node (ref "U$6") (pin "P$3") (pinfunction "OUT+_P$3") (pintype "bidirectional"))
    )
    (net (code "44") (name "Net-(IC2-IN-)") (class "Default")
      (node (ref "IC2") (pin "4") (pinfunction "IN-_4") (pintype "input"))
      (node (ref "R3") (pin "2") (pinfunction "2_2") (pintype "passive"))
      (node (ref "SERVO_2") (pin "2") (pinfunction "2_2") (pintype "passive"))
    )
    (net (code "45") (name "Net-(IC3-IN+)") (class "Default")
      (node (ref "C14") (pin "1") (pinfunction "1_1") (pintype "passive"))
      (node (ref "IC3") (pin "3") (pinfunction "IN+_3") (pintype "input"))
      (node (ref "IC3") (pin "5") (pinfunction "V+_5") (pintype "power_in"))
      (node (ref "R5") (pin "1") (pinfunction "1_1") (pintype "passive"))
      (node (ref "U$7") (pin "P$3") (pinfunction "OUT+_P$3") (pintype "bidirectional"))
    )
    (net (code "46") (name "Net-(IC3-IN-)") (class "Default")
      (node (ref "IC3") (pin "4") (pinfunction "IN-_4") (pintype "input"))
      (node (ref "R5") (pin "2") (pinfunction "2_2") (pintype "passive"))
      (node (ref "SERVO_3") (pin "2") (pinfunction "2_2") (pintype "passive"))
    )
    (net (code "47") (name "Net-(IC4-IN+)") (class "Default")
      (node (ref "C15") (pin "1") (pinfunction "1_1") (pintype "passive"))
      (node (ref "IC4") (pin "3") (pinfunction "IN+_3") (pintype "input"))
      (node (ref "IC4") (pin "5") (pinfunction "V+_5") (pintype "power_in"))
      (node (ref "R7") (pin "1") (pinfunction "1_1") (pintype "passive"))
      (node (ref "U$8") (pin "P$3") (pinfunction "OUT+_P$3") (pintype "bidirectional"))
    )
    (net (code "48") (name "Net-(IC4-IN-)") (class "Default")
      (node (ref "IC4") (pin "4") (pinfunction "IN-_4") (pintype "input"))
      (node (ref "R7") (pin "2") (pinfunction "2_2") (pintype "passive"))
      (node (ref "SERVO_4") (pin "2") (pinfunction "2_2") (pintype "passive"))
    )
    (net (code "49") (name "Net-(IC5-IN+)") (class "Default")
      (node (ref "C16") (pin "1") (pinfunction "1_1") (pintype "passive"))
      (node (ref "IC5") (pin "3") (pinfunction "IN+_3") (pintype "input"))
      (node (ref "IC5") (pin "5") (pinfunction "V+_5") (pintype "power_in"))
      (node (ref "R9") (pin "1") (pinfunction "1_1") (pintype "passive"))
      (node (ref "U$9") (pin "P$3") (pinfunction "OUT+_P$3") (pintype "bidirectional"))
    )
    (net (code "50") (name "Net-(IC5-IN-)") (class "Default")
      (node (ref "IC5") (pin "4") (pinfunction "IN-_4") (pintype "input"))
      (node (ref "R9") (pin "2") (pinfunction "2_2") (pintype "passive"))
      (node (ref "SERVO_5") (pin "2") (pinfunction "2_2") (pintype "passive"))
    )
    (net (code "51") (name "Net-(IC6-IN+)") (class "Default")
      (node (ref "C17") (pin "1") (pinfunction "1_1") (pintype "passive"))
      (node (ref "IC6") (pin "3") (pinfunction "IN+_3") (pintype "input"))
      (node (ref "IC6") (pin "5") (pinfunction "V+_5") (pintype "power_in"))
      (node (ref "R11") (pin "1") (pinfunction "1_1") (pintype "passive"))
      (node (ref "U$10") (pin "P$3") (pinfunction "OUT+_P$3") (pintype "bidirectional"))
    )
    (net (code "52") (name "Net-(IC6-IN-)") (class "Default")
      (node (ref "IC6") (pin "4") (pinfunction "IN-_4") (pintype "input"))
      (node (ref "R11") (pin "2") (pinfunction "2_2") (pintype "passive"))
      (node (ref "SERVO_6") (pin "2") (pinfunction "2_2") (pintype "passive"))
    )
    (net (code "53") (name "Net-(IC7A-CLK)") (class "Default")
      (node (ref "IC7") (pin "14") (pinfunction "CLK_14") (pintype "input"))
      (node (ref "U$1") (pin "6") (pinfunction "6_6") (pintype "bidirectional"))
    )
    (net (code "54") (name "Net-(IC7A-RES)") (class "Default")
      (node (ref "IC7") (pin "15") (pinfunction "RES_15") (pintype "input"))
      (node (ref "U$1") (pin "7") (pinfunction "7_7") (pintype "bidirectional"))
    )
    (net (code "55") (name "Net-(Q1-G)") (class "Default")
      (node (ref "Q1") (pin "1") (pinfunction "G_1") (pintype "passive"))
      (node (ref "R13") (pin "2") (pinfunction "2_2") (pintype "passive"))
      (node (ref "R14") (pin "1") (pinfunction "1_1") (pintype "passive"))
    )
    (net (code "56") (name "Net-(U$4-P$3)") (class "Default")
      (node (ref "U$4") (pin "P$4") (pinfunction "P$3_P$4") (pintype "bidirectional"))
      (node (ref "X11") (pin "2") (pinfunction "KL_2") (pintype "passive"))
    )
    (net (code "57") (name "Net-(X8B-KL)") (class "Default")
      (node (ref "D4") (pin "A") (pinfunction "A_A") (pintype "passive"))
      (node (ref "X8") (pin "2") (pinfunction "KL_2") (pintype "passive"))
    )
    (net (code "58") (name "unconnected-(IC7A-CO-Pad12)") (class "Default")
      (node (ref "IC7") (pin "12") (pinfunction "CO_12") (pintype "output"))
    )
    (net (code "59") (name "unconnected-(IC7A-Q6-Pad5)") (class "Default")
      (node (ref "IC7") (pin "5") (pinfunction "Q6_5") (pintype "output"))
    )
    (net (code "60") (name "unconnected-(IC7A-Q7-Pad6)") (class "Default")
      (node (ref "IC7") (pin "6") (pinfunction "Q7_6") (pintype "output"))
    )
    (net (code "61") (name "unconnected-(IC7A-Q8-Pad9)") (class "Default")
      (node (ref "IC7") (pin "9") (pinfunction "Q8_9") (pintype "output"))
    )
    (net (code "62") (name "unconnected-(IC7A-Q9-Pad11)") (class "Default")
      (node (ref "IC7") (pin "11") (pinfunction "Q9_11") (pintype "output"))
    )
    (net (code "63") (name "unconnected-(IC8-CH6-Pad7)") (class "Default")
      (node (ref "IC8") (pin "7") (pinfunction "CH6_7") (pintype "input"))
    )
    (net (code "64") (name "unconnected-(IC8-CH7-Pad8)") (class "Default")
      (node (ref "IC8") (pin "8") (pinfunction "CH7_8") (pintype "input"))
    )
    (net (code "65") (name "unconnected-(U$1-Pad5)") (class "Default")
      (node (ref "U$1") (pin "5") (pinfunction "5_5") (pintype "bidirectional"))
    )
    (net (code "66") (name "unconnected-(U$1-PadA6)") (class "Default")
      (node (ref "U$1") (pin "A6") (pinfunction "A6_A6") (pintype "bidirectional"))
    )
    (net (code "67") (name "unconnected-(U$1-PadA7)") (class "Default")
      (node (ref "U$1") (pin "A7") (pinfunction "A7_A7") (pintype "bidirectional"))
    )
    (net (code "68") (name "unconnected-(U$1-PadRAW)") (class "Default")
      (node (ref "U$1") (pin "RAW") (pinfunction "RAW_RAW") (pintype "bidirectional"))
    )
    (net (code "69") (name "unconnected-(U$1-PadRST)") (class "Default")
      (node (ref "U$1") (pin "RST") (pinfunction "RST_RST") (pintype "bidirectional"))
    )
    (net (code "70") (name "unconnected-(U$1-RX1-PadRXI)") (class "Default")
      (node (ref "U$1") (pin "RXI") (pinfunction "RX1_RXI") (pintype "bidirectional"))
    )
    (net (code "71") (name "unconnected-(U$1-TX0-PadTXD)") (class "Default")
      (node (ref "U$1") (pin "TXD") (pinfunction "TX0_TXD") (pintype "bidirectional"))
    )
    (net (code "72") (name "unconnected-(X1-C5-PadC5.1)") (class "Default")
      (node (ref "X1") (pin "C5.1") (pinfunction "C5_C5.1") (pintype "passive"))
    )
    (net (code "73") (name "unconnected-(X1-Pad5)") (class "Default")
      (node (ref "X1") (pin "5") (pinfunction "5_5") (pintype "passive"))
    )
    (net (code "74") (name "unconnected-(X1-PadC1)") (class "Default")
      (node (ref "X1") (pin "C1") (pinfunction "C1_C1") (pintype "passive"))
    )
    (net (code "75") (name "unconnected-(X1-PadC2)") (class "Default")
      (node (ref "X1") (pin "C2") (pinfunction "C2_C2") (pintype "passive"))
    )
    (net (code "76") (name "unconnected-(X1-PadC3)") (class "Default")
      (node (ref "X1") (pin "C3") (pinfunction "C3_C3") (pintype "passive"))
    )
    (net (code "77") (name "unconnected-(X1-PadC4)") (class "Default")
      (node (ref "X1") (pin "C4") (pinfunction "C4_C4") (pintype "passive"))
    )
    (net (code "78") (name "unconnected-(X1-PadC5.2)") (class "Default")
      (node (ref "X1") (pin "C5.2") (pinfunction "C5.2_C5.2") (pintype "passive"))
    )
  )
)
